# IMU_Module.net
KiCad netlist of a schematic drawn in EasyEDA Pro
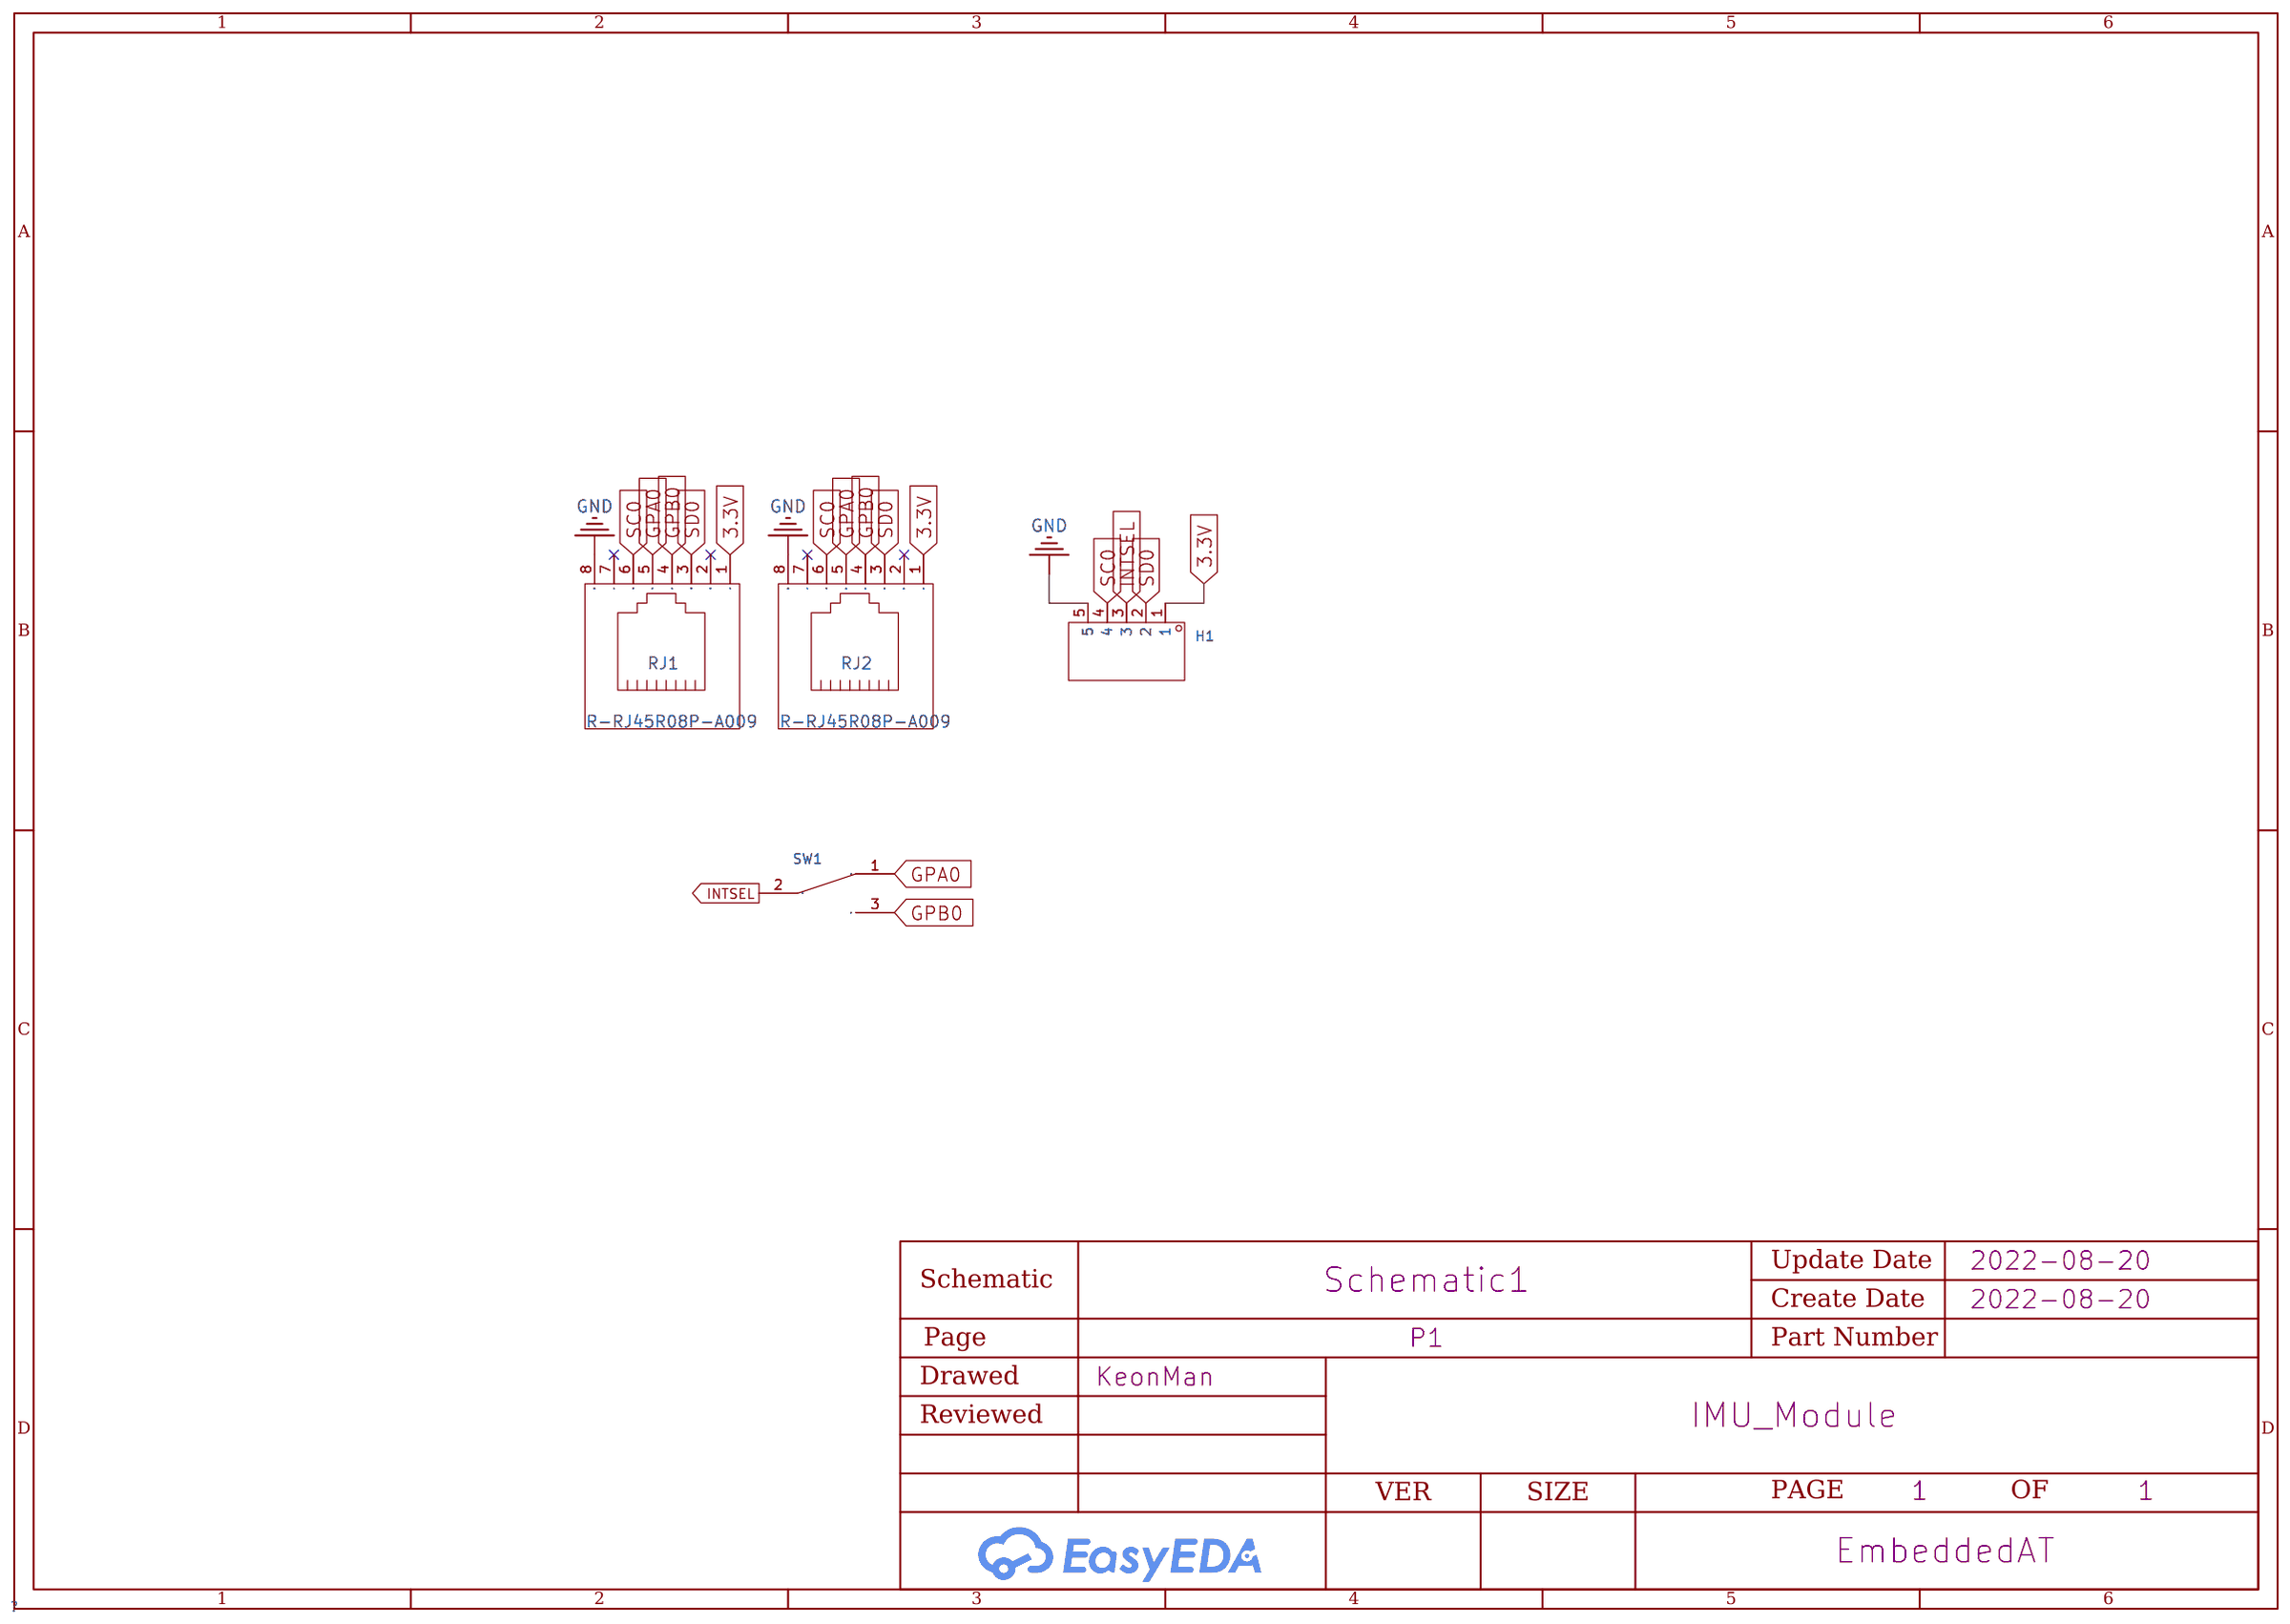
[diagram p0: schematic sheet]

(export (version "E")
  (design (tool "Eeschema 10.0.6"))
  (components
    (comp (ref "H1")
      (value "~")
      (footprint "easyedapro:HDR-TH_5P-P2.54-V-M")
      (fields (field (name "Manufacturer Part") "B-2100S05P-A110") (field (name "Manufacturer") "Ckmtw(灿科盟)"))
      (libsource (lib "easyedapro") (part "210S-1*5P L=11.6MMGold-plated black"))
    )
    (comp (ref "RJ1")
      (value "R-RJ45R08P-A009")
      (footprint "easyedapro:RJ45-TH_R-RJ45R08P-A009")
      (fields (field (name "Manufacturer") "Ckmtw(灿科盟)"))
      (libsource (lib "easyedapro") (part "R-RJ45R08P-A009"))
    )
    (comp (ref "RJ2")
      (value "R-RJ45R08P-A009")
      (footprint "easyedapro:RJ45-TH_R-RJ45R08P-A009")
      (fields (field (name "Manufacturer") "Ckmtw(灿科盟)"))
      (libsource (lib "easyedapro") (part "R-RJ45R08P-A009"))
    )
    (comp (ref "SW1")
      (value "~")
      (footprint "easyedapro:SW-TH_EG1218")
      (description "额定电压 DC:30V;触点额定电流:200mA @ 30VDC;开关功能:On-On;电路结构:SPDT;额定电压 AC:-;")
      (fields (field (name "Manufacturer Part") "EG1218") (field (name "Manufacturer") "E-Switch"))
      (libsource (lib "easyedapro") (part "EG1218"))
    )
  )
  (nets
    (net (code "1") (name "3.3V") (class "Default")
      (node (ref "H1") (pin "1") (pinfunction "1_1") (pintype "input"))
      (node (ref "RJ1") (pin "1") (pinfunction "1_1") (pintype "input"))
      (node (ref "RJ2") (pin "1") (pinfunction "1_1") (pintype "input"))
    )
    (net (code "2") (name "GND") (class "Default")
      (node (ref "H1") (pin "5") (pinfunction "5_5") (pintype "input"))
      (node (ref "RJ1") (pin "8") (pinfunction "8_8") (pintype "input"))
      (node (ref "RJ2") (pin "8") (pinfunction "8_8") (pintype "input"))
    )
    (net (code "3") (name "GPA0") (class "Default")
      (node (ref "RJ1") (pin "5") (pinfunction "5_5") (pintype "input"))
      (node (ref "RJ2") (pin "5") (pinfunction "5_5") (pintype "input"))
      (node (ref "SW1") (pin "1") (pinfunction "1_1") (pintype "input"))
    )
    (net (code "4") (name "GPB0") (class "Default")
      (node (ref "RJ1") (pin "4") (pinfunction "4_4") (pintype "input"))
      (node (ref "RJ2") (pin "4") (pinfunction "4_4") (pintype "input"))
      (node (ref "SW1") (pin "3") (pinfunction "3_3") (pintype "input"))
    )
    (net (code "5") (name "INTSEL") (class "Default")
      (node (ref "H1") (pin "3") (pinfunction "3_3") (pintype "input"))
      (node (ref "SW1") (pin "2") (pinfunction "2_2") (pintype "input"))
    )
    (net (code "6") (name "SC0") (class "Default")
      (node (ref "H1") (pin "4") (pinfunction "4_4") (pintype "input"))
      (node (ref "RJ1") (pin "6") (pinfunction "6_6") (pintype "input"))
      (node (ref "RJ2") (pin "6") (pinfunction "6_6") (pintype "input"))
    )
    (net (code "7") (name "SD0") (class "Default")
      (node (ref "H1") (pin "2") (pinfunction "2_2") (pintype "input"))
      (node (ref "RJ1") (pin "3") (pinfunction "3_3") (pintype "input"))
      (node (ref "RJ2") (pin "3") (pinfunction "3_3") (pintype "input"))
    )
    (net (code "8") (name "unconnected-(RJ1-Pad2)") (class "Default")
      (node (ref "RJ1") (pin "2") (pinfunction "2_2") (pintype "input+no_connect"))
    )
    (net (code "9") (name "unconnected-(RJ1-Pad7)") (class "Default")
      (node (ref "RJ1") (pin "7") (pinfunction "7_7") (pintype "input+no_connect"))
    )
    (net (code "10") (name "unconnected-(RJ2-Pad2)") (class "Default")
      (node (ref "RJ2") (pin "2") (pinfunction "2_2") (pintype "input+no_connect"))
    )
    (net (code "11") (name "unconnected-(RJ2-Pad7)") (class "Default")
      (node (ref "RJ2") (pin "7") (pinfunction "7_7") (pintype "input+no_connect"))
    )
  )
)
